# CONN.net
KiCad netlist of a schematic drawn in Altium Designer
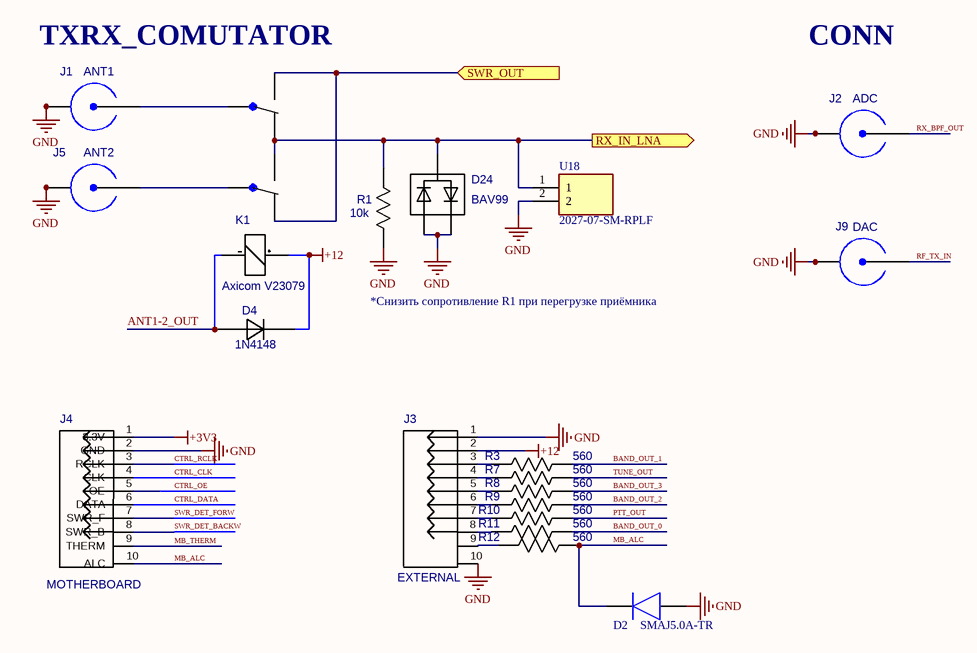
[diagram p0: CONN.SchDoc]

(export (version "E")
  (design (tool "Eeschema 10.0.6"))
  (components
    (comp (ref "D2")
      (value "SMAJ5.0A-TR")
      (footprint "SamacSys:SMBJ36CATR")
      (description "Diode")
      (fields
        (field (name "MANUFACTURER_PART_NUMBER") "SMLVT3V3")
        (field (name "MOUSER PART NUMBER") "511-SMLVT3V3")
      )
      (libsource (lib "*") (part "SMLVT3V3"))
    )
    (comp (ref "D4") (value "1N4148") (footprint "1N4148") (libsource (lib "*") (part "1N4148")))
    (comp (ref "D24") (value "BAV99") (footprint "SOT23") (libsource (lib "*") (part "BAV99")))
    (comp (ref "J1")
      (value "ANT1")
      (footprint "31-5431")
      (description "SMA")
      (libsource (lib "RF-UNIT_1") (part "31-5431"))
    )
    (comp (ref "J2")
      (value "ADC")
      (footprint "31-5431")
      (description "SMA")
      (libsource (lib "RF-UNIT_1") (part "31-5431"))
    )
    (comp (ref "J3")
      (value "EXTERNAL")
      (footprint "90131-0126")
      (description "2*5 PIN")
      (libsource (lib "RF-UNIT") (part "90131-0126"))
    )
    (comp (ref "J4")
      (value "MOTHERBOARD")
      (footprint "90131-0126")
      (description "2*5 PIN")
      (libsource (lib "") (part "90131-0126_1"))
    )
    (comp (ref "J5")
      (value "ANT2")
      (footprint "31-5431")
      (description "SMA")
      (libsource (lib "RF-UNIT_1") (part "31-5431"))
    )
    (comp (ref "J9")
      (value "DAC")
      (footprint "31-5431")
      (description "SMA")
      (libsource (lib "RF-UNIT_1") (part "31-5431"))
    )
    (comp (ref "K1")
      (value "Axicom V23079")
      (footprint "V23079")
      (libsource (lib "RF-UNIT") (part "Axicom V23079"))
    )
    (comp (ref "R1")
      (value "10k")
      (footprint "RES_1206")
      (description "RES_1206")
      (libsource (lib "*") (part "RES_1206"))
    )
    (comp (ref "R3")
      (value "560")
      (footprint "RES_0805")
      (description "RES_0805")
      (libsource (lib "*") (part "RES_0805"))
    )
    (comp (ref "R7")
      (value "560")
      (footprint "RES_0805")
      (description "RES_0805")
      (libsource (lib "*") (part "RES_0805"))
    )
    (comp (ref "R8")
      (value "560")
      (footprint "RES_0805")
      (description "RES_0805")
      (libsource (lib "*") (part "RES_0805"))
    )
    (comp (ref "R9")
      (value "560")
      (footprint "RES_0805")
      (description "RES_0805")
      (libsource (lib "*") (part "RES_0805"))
    )
    (comp (ref "R10")
      (value "560")
      (footprint "RES_0805")
      (description "RES_0805")
      (libsource (lib "*") (part "RES_0805"))
    )
    (comp (ref "R11")
      (value "560")
      (footprint "RES_0805")
      (description "RES_0805")
      (libsource (lib "*") (part "RES_0805"))
    )
    (comp (ref "R12")
      (value "560")
      (footprint "RES_0805")
      (description "RES_0805")
      (libsource (lib "*") (part "RES_0805"))
    )
    (comp (ref "U18")
      (value "2027-07-SM-RPLF")
      (footprint "SamacSys:200307SMRPLF")
      (fields
        (field (name "MANUFACTURER_PART_NUMBER") "2003-07-SM-RPLF")
        (field (name "MOUSER PART NUMBER") "652-2003-07-SM-RPLF")
      )
      (libsource (lib "*") (part "2003-07-SM-RPLF"))
    )
  )
  (nets
    (net (code "1") (name "+3V3") (class "Default")
      (node (ref "J4") (pin "1") (pinfunction "3.3V_1") (pintype "passive"))
    )
    (net (code "2") (name "+12") (class "Default")
      (node (ref "D4") (pin "1") (pinfunction "K_1") (pintype "passive"))
      (node (ref "J3") (pin "2") (pinfunction "12V_2") (pintype "passive"))
      (node (ref "K1") (pin "1") (pinfunction "+_1") (pintype "passive"))
    )
    (net (code "4") (name "/ANT1-2_OUT") (class "Default")
      (node (ref "D4") (pin "2") (pinfunction "A_2") (pintype "passive"))
      (node (ref "K1") (pin "8") (pinfunction "-_8") (pintype "passive"))
    )
    (net (code "5") (name "/BAND_OUT_0") (class "Default")
      (node (ref "R11") (pin "2") (pinfunction "2_2") (pintype "passive"))
    )
    (net (code "6") (name "/BAND_OUT_1") (class "Default")
      (node (ref "R3") (pin "2") (pinfunction "2_2") (pintype "passive"))
    )
    (net (code "7") (name "/BAND_OUT_2") (class "Default")
      (node (ref "R9") (pin "2") (pinfunction "2_2") (pintype "passive"))
    )
    (net (code "8") (name "/BAND_OUT_3") (class "Default")
      (node (ref "R8") (pin "2") (pinfunction "2_2") (pintype "passive"))
    )
    (net (code "9") (name "/CTRL_CLK") (class "Default")
      (node (ref "J4") (pin "4") (pinfunction "CLK_4") (pintype "passive"))
    )
    (net (code "10") (name "/CTRL_DATA") (class "Default")
      (node (ref "J4") (pin "6") (pinfunction "DATA_6") (pintype "passive"))
    )
    (net (code "11") (name "/CTRL_OE") (class "Default")
      (node (ref "J4") (pin "5") (pinfunction "OE_5") (pintype "passive"))
    )
    (net (code "12") (name "/CTRL_RCLK") (class "Default")
      (node (ref "J4") (pin "3") (pinfunction "RCLK_3") (pintype "passive"))
    )
    (net (code "13") (name "/MB_ALC") (class "Default")
      (node (ref "D2") (pin "1") (pinfunction "K_1") (pintype "passive"))
      (node (ref "J4") (pin "10") (pinfunction "ALC_10") (pintype "passive"))
      (node (ref "R12") (pin "2") (pinfunction "2_2") (pintype "passive"))
    )
    (net (code "14") (name "/MB_THERM") (class "Default")
      (node (ref "J4") (pin "9") (pinfunction "THERM_9") (pintype "passive"))
    )
    (net (code "15") (name "/PTT_OUT") (class "Default")
      (node (ref "R10") (pin "2") (pinfunction "2_2") (pintype "passive"))
    )
    (net (code "16") (name "/RF_TX_IN") (class "Default")
      (node (ref "J9") (pin "5") (pinfunction "CON_5") (pintype "passive"))
    )
    (net (code "17") (name "/RX_BPF_OUT") (class "Default")
      (node (ref "J2") (pin "5") (pinfunction "CON_5") (pintype "passive"))
    )
    (net (code "18") (name "/RX_IN_LNA") (class "Default")
      (node (ref "D24") (pin "3") (pinfunction "C(D1),A(D2)_3") (pintype "passive"))
      (node (ref "K1") (pin "4") (pinfunction "S_4") (pintype "passive"))
      (node (ref "K1") (pin "7") (pinfunction "O_7") (pintype "passive"))
      (node (ref "R1") (pin "2") (pinfunction "2_2") (pintype "passive"))
      (node (ref "U18") (pin "1") (pinfunction "1_1") (pintype "passive"))
    )
    (net (code "19") (name "/SWR_DET_BACKW") (class "Default")
      (node (ref "J4") (pin "8") (pinfunction "SWR_B_8") (pintype "passive"))
    )
    (net (code "20") (name "/SWR_DET_FORW") (class "Default")
      (node (ref "J4") (pin "7") (pinfunction "SWR_F_7") (pintype "passive"))
    )
    (net (code "21") (name "/SWR_OUT") (class "Default")
      (node (ref "K1") (pin "2") (pinfunction "O_2") (pintype "passive"))
      (node (ref "K1") (pin "5") (pinfunction "S_5") (pintype "passive"))
    )
    (net (code "22") (name "/TUNE_OUT") (class "Default")
      (node (ref "R7") (pin "2") (pinfunction "2_2") (pintype "passive"))
    )
    (net (code "23") (name "GND") (class "Default")
      (node (ref "D2") (pin "2") (pinfunction "A_2") (pintype "passive"))
      (node (ref "D24") (pin "1") (pinfunction "A(D1)_1") (pintype "passive"))
      (node (ref "D24") (pin "2") (pinfunction "C(D2)_2") (pintype "passive"))
      (node (ref "J1") (pin "1") (pinfunction "GND_1") (pintype "passive"))
      (node (ref "J1") (pin "2") (pinfunction "GND_2") (pintype "passive"))
      (node (ref "J1") (pin "3") (pinfunction "GND_3") (pintype "passive"))
      (node (ref "J1") (pin "4") (pinfunction "GND_4") (pintype "passive"))
      (node (ref "J2") (pin "1") (pinfunction "GND_1") (pintype "passive"))
      (node (ref "J2") (pin "2") (pinfunction "GND_2") (pintype "passive"))
      (node (ref "J2") (pin "3") (pinfunction "GND_3") (pintype "passive"))
      (node (ref "J2") (pin "4") (pinfunction "GND_4") (pintype "passive"))
      (node (ref "J3") (pin "1") (pinfunction "GND_1") (pintype "passive"))
      (node (ref "J3") (pin "10") (pinfunction "GND_10") (pintype "passive"))
      (node (ref "J4") (pin "2") (pinfunction "GND_2") (pintype "passive"))
      (node (ref "J5") (pin "1") (pinfunction "GND_1") (pintype "passive"))
      (node (ref "J5") (pin "2") (pinfunction "GND_2") (pintype "passive"))
      (node (ref "J5") (pin "3") (pinfunction "GND_3") (pintype "passive"))
      (node (ref "J5") (pin "4") (pinfunction "GND_4") (pintype "passive"))
      (node (ref "J9") (pin "1") (pinfunction "GND_1") (pintype "passive"))
      (node (ref "J9") (pin "2") (pinfunction "GND_2") (pintype "passive"))
      (node (ref "J9") (pin "3") (pinfunction "GND_3") (pintype "passive"))
      (node (ref "J9") (pin "4") (pinfunction "GND_4") (pintype "passive"))
      (node (ref "R1") (pin "1") (pinfunction "1_1") (pintype "passive"))
      (node (ref "U18") (pin "2") (pinfunction "2_2") (pintype "passive"))
    )
    (net (code "24") (name "Net-(J1-CON)") (class "Default")
      (node (ref "J1") (pin "5") (pinfunction "CON_5") (pintype "passive"))
      (node (ref "K1") (pin "6") (pinfunction "P_6") (pintype "passive"))
    )
    (net (code "25") (name "Net-(J3-ALC_IN)") (class "Default")
      (node (ref "J3") (pin "9") (pinfunction "ALC_IN_9") (pintype "passive"))
      (node (ref "R12") (pin "1") (pinfunction "1_1") (pintype "passive"))
    )
    (net (code "26") (name "Net-(J3-BAND0)") (class "Default")
      (node (ref "J3") (pin "8") (pinfunction "BAND0_8") (pintype "passive"))
      (node (ref "R11") (pin "1") (pinfunction "1_1") (pintype "passive"))
    )
    (net (code "27") (name "Net-(J3-BAND1)") (class "Default")
      (node (ref "J3") (pin "3") (pinfunction "BAND1_3") (pintype "passive"))
      (node (ref "R3") (pin "1") (pinfunction "1_1") (pintype "passive"))
    )
    (net (code "28") (name "Net-(J3-BAND2)") (class "Default")
      (node (ref "J3") (pin "6") (pinfunction "BAND2_6") (pintype "passive"))
      (node (ref "R9") (pin "1") (pinfunction "1_1") (pintype "passive"))
    )
    (net (code "29") (name "Net-(J3-BAND3)") (class "Default")
      (node (ref "J3") (pin "5") (pinfunction "BAND3_5") (pintype "passive"))
      (node (ref "R8") (pin "1") (pinfunction "1_1") (pintype "passive"))
    )
    (net (code "30") (name "Net-(J3-PTT_OUT)") (class "Default")
      (node (ref "J3") (pin "7") (pinfunction "PTT_OUT_7") (pintype "passive"))
      (node (ref "R10") (pin "1") (pinfunction "1_1") (pintype "passive"))
    )
    (net (code "31") (name "Net-(J3-TUNE_OUT)") (class "Default")
      (node (ref "J3") (pin "4") (pinfunction "TUNE_OUT_4") (pintype "passive"))
      (node (ref "R7") (pin "1") (pinfunction "1_1") (pintype "passive"))
    )
    (net (code "32") (name "Net-(J5-CON)") (class "Default")
      (node (ref "J5") (pin "5") (pinfunction "CON_5") (pintype "passive"))
      (node (ref "K1") (pin "3") (pinfunction "P_3") (pintype "passive"))
    )
  )
)
